# EEZ_Mosfet_pre-regulator_r3B3b_SS.net
KiCad netlist of a schematic drawn in EAGLE
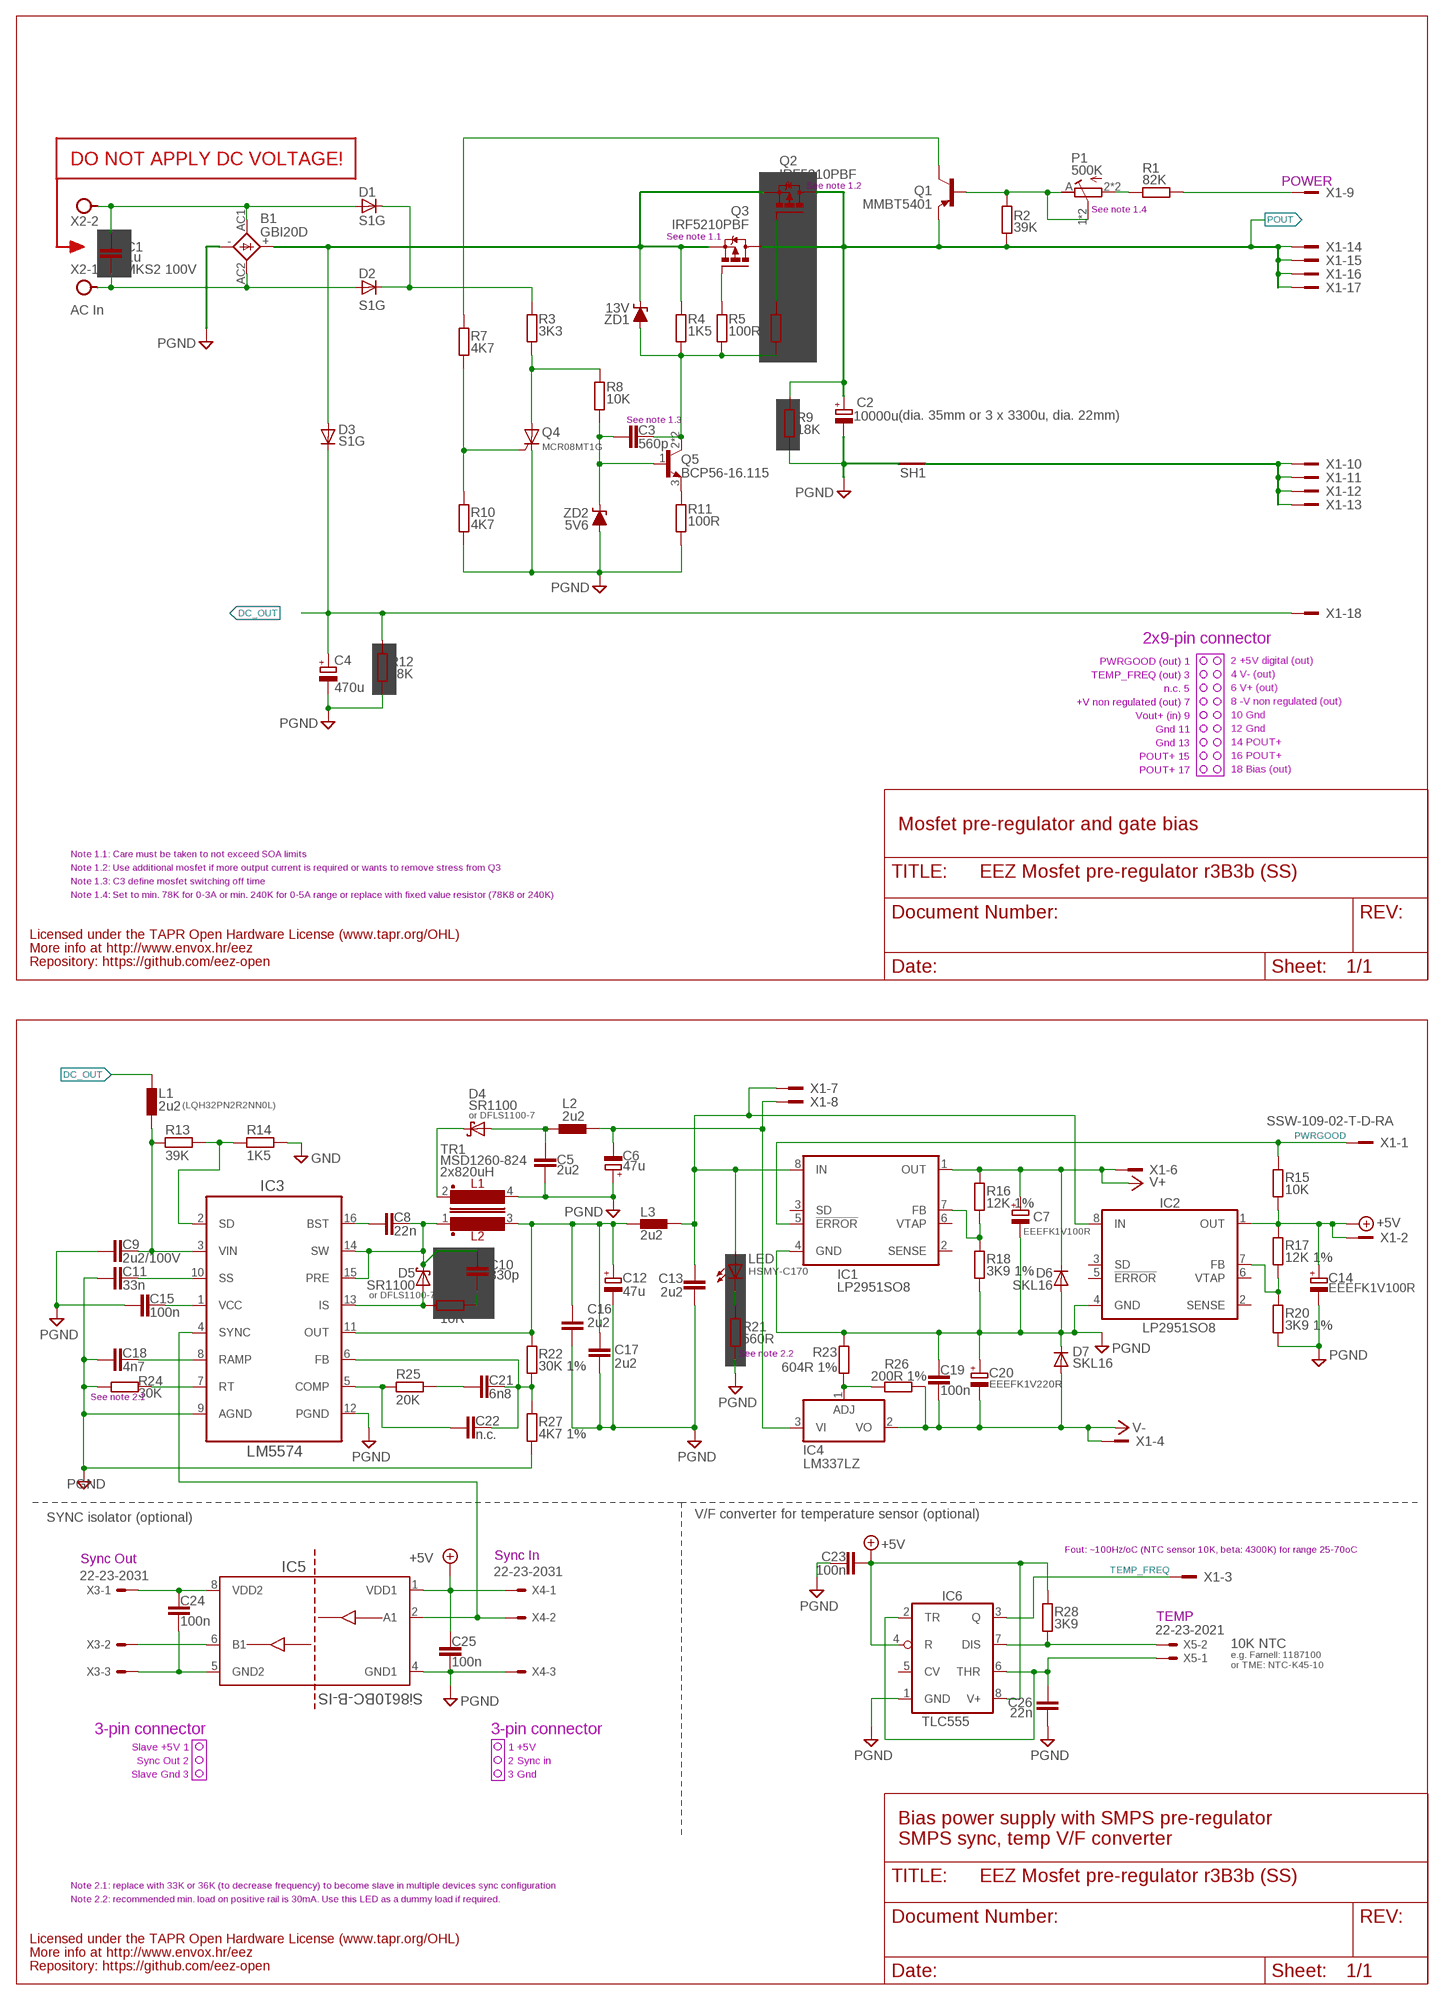
[diagram p0: schematic, sheet 1]

(export (version "E")
  (design (tool "Eeschema 10.0.6"))
  (components
    (comp (ref "B1")
      (value "GBI20D")
      (footprint "eagle-import:GBI20")
      (libsource (lib "eagle-import") (part "BRIDGEDIOTEC"))
    )
    (comp (ref "C1")
      (value "1u")
      (footprint "eagle-import:C050-075X075")
      (libsource (lib "eagle-import") (part "C-EU050-075X075"))
    )
    (comp (ref "C2")
      (value "10000u")
      (footprint "eagle-import:ED35D+3XED22.5_COMBO")
      (libsource (lib "eagle-import") (part "ECAP35+3X22.5"))
    )
    (comp (ref "C3")
      (value "560p")
      (footprint "eagle-import:C0805")
      (libsource (lib "eagle-import") (part "C-EUC0805"))
    )
    (comp (ref "C4")
      (value "470u")
      (footprint "eagle-import:ECAP5_13")
      (libsource (lib "eagle-import") (part "ECAP5G_13MM"))
    )
    (comp (ref "C5")
      (value "2u2")
      (footprint "eagle-import:C1210")
      (libsource (lib "eagle-import") (part "C-EUC1210"))
    )
    (comp (ref "C6")
      (value "47u")
      (footprint "eagle-import:CAPAE660X610N_COMBO")
      (libsource (lib "eagle-import") (part "ECAPEEEFK+8.5MM"))
    )
    (comp (ref "C7")
      (value "EEEFK1V100R")
      (footprint "eagle-import:CAPAE430X610N_COMBO")
      (libsource (lib "eagle-import") (part "ECAPEEEFK+5MM"))
    )
    (comp (ref "C8")
      (value "22n")
      (footprint "eagle-import:C0805")
      (libsource (lib "eagle-import") (part "C-EUC0805"))
    )
    (comp (ref "C9")
      (value "2u2/100V")
      (footprint "eagle-import:C1210")
      (libsource (lib "eagle-import") (part "C-EUC1210"))
    )
    (comp (ref "C10")
      (value "330p")
      (footprint "eagle-import:C0805")
      (libsource (lib "eagle-import") (part "C-EUC0805"))
    )
    (comp (ref "C11")
      (value "33n")
      (footprint "eagle-import:C0805")
      (libsource (lib "eagle-import") (part "C-EUC0805"))
    )
    (comp (ref "C12")
      (value "47u")
      (footprint "eagle-import:CAPAE660X610N_COMBO")
      (libsource (lib "eagle-import") (part "ECAPEEEFK+8.5MM"))
    )
    (comp (ref "C13")
      (value "2u2")
      (footprint "eagle-import:C1210")
      (libsource (lib "eagle-import") (part "C-EUC1210"))
    )
    (comp (ref "C14")
      (value "EEEFK1V100R")
      (footprint "eagle-import:CAPAE430X610N_COMBO")
      (libsource (lib "eagle-import") (part "ECAPEEEFK+5MM"))
    )
    (comp (ref "C15")
      (value "100n")
      (footprint "eagle-import:C0805")
      (libsource (lib "eagle-import") (part "C-EUC0805"))
    )
    (comp (ref "C16")
      (value "2u2")
      (footprint "eagle-import:C1210")
      (libsource (lib "eagle-import") (part "C-EUC1210"))
    )
    (comp (ref "C17")
      (value "2u2")
      (footprint "eagle-import:C1210")
      (libsource (lib "eagle-import") (part "C-EUC1210"))
    )
    (comp (ref "C18")
      (value "4n7")
      (footprint "eagle-import:C0805")
      (libsource (lib "eagle-import") (part "C-EUC0805"))
    )
    (comp (ref "C19")
      (value "100n")
      (footprint "eagle-import:C0805")
      (libsource (lib "eagle-import") (part "C-EUC0805"))
    )
    (comp (ref "C20")
      (value "EEEFK1V220R")
      (footprint "eagle-import:CAPAE430X610N_COMBO")
      (libsource (lib "eagle-import") (part "ECAPEEEFK+5MM"))
    )
    (comp (ref "C21")
      (value "6n8")
      (footprint "eagle-import:C0805")
      (libsource (lib "eagle-import") (part "C-EUC0805"))
    )
    (comp (ref "C22")
      (value "n.c.")
      (footprint "eagle-import:C0805")
      (libsource (lib "eagle-import") (part "C-EUC0805"))
    )
    (comp (ref "C23")
      (value "100n")
      (footprint "eagle-import:C0603")
      (libsource (lib "eagle-import") (part "C-EUC0603"))
    )
    (comp (ref "C24")
      (value "100n")
      (footprint "eagle-import:C0603")
      (libsource (lib "eagle-import") (part "C-EUC0603"))
    )
    (comp (ref "C25")
      (value "100n")
      (footprint "eagle-import:C0603")
      (libsource (lib "eagle-import") (part "C-EUC0603"))
    )
    (comp (ref "C26")
      (value "22n")
      (footprint "eagle-import:C0805")
      (libsource (lib "eagle-import") (part "C-EUC0805"))
    )
    (comp (ref "D1")
      (value "S1G")
      (footprint "eagle-import:DO214AC")
      (libsource (lib "eagle-import") (part "DIODE-DO214AC"))
    )
    (comp (ref "D2")
      (value "S1G")
      (footprint "eagle-import:DO214AC")
      (libsource (lib "eagle-import") (part "DIODE-DO214AC"))
    )
    (comp (ref "D3")
      (value "S1G")
      (footprint "eagle-import:DO214AC")
      (libsource (lib "eagle-import") (part "DIODE-DO214AC"))
    )
    (comp (ref "D4")
      (value "SR1100")
      (footprint "eagle-import:DO34+SOD123")
      (libsource (lib "eagle-import") (part "SCHOTTKYDO34+SOD123"))
    )
    (comp (ref "D5")
      (value "SR1100")
      (footprint "eagle-import:DO34+SOD123")
      (libsource (lib "eagle-import") (part "SCHOTTKYDO34+SOD123"))
    )
    (comp (ref "D6")
      (value "SKL16")
      (footprint "eagle-import:DO214AC")
      (libsource (lib "eagle-import") (part "DIODE-DO214AC"))
    )
    (comp (ref "D7")
      (value "SKL16")
      (footprint "eagle-import:DO214AC")
      (libsource (lib "eagle-import") (part "DIODE-DO214AC"))
    )
    (comp (ref "IC1")
      (value "LP2951SO8")
      (footprint "eagle-import:SOIC127P600X175-8N")
      (libsource (lib "eagle-import") (part "LP2951SO8"))
    )
    (comp (ref "IC2")
      (value "LP2951SO8")
      (footprint "eagle-import:SOIC127P600X175-8N")
      (libsource (lib "eagle-import") (part "LP2951SO8"))
    )
    (comp (ref "IC3")
      (value "LM5574")
      (footprint "eagle-import:SOP65P640X110-16N")
      (fields (field (name "MPN") "LM5574MT"))
      (libsource (lib "eagle-import") (part "LM5574"))
    )
    (comp (ref "IC4")
      (value "LM337LZ")
      (footprint "eagle-import:TO92")
      (libsource (lib "eagle-import") (part "337LZLM"))
    )
    (comp (ref "IC5")
      (value "Si8610BC-B-IS")
      (footprint "eagle-import:SOIC127P600X173-8N")
      (libsource (lib "eagle-import") (part "SI8610"))
    )
    (comp (ref "IC6")
      (value "TLC555")
      (footprint "eagle-import:SOIC127P600X175-8N")
      (libsource (lib "eagle-import") (part "LM555SOIC8"))
    )
    (comp (ref "L1")
      (value "2u2")
      (footprint "eagle-import:L1210_COMBO")
      (libsource (lib "eagle-import") (part "L1210COMBO"))
    )
    (comp (ref "L2")
      (value "2u2")
      (footprint "eagle-import:L1210_COMBO")
      (libsource (lib "eagle-import") (part "L1210COMBO"))
    )
    (comp (ref "L3")
      (value "2u2")
      (footprint "eagle-import:L1210_COMBO")
      (libsource (lib "eagle-import") (part "L1210COMBO"))
    )
    (comp (ref "LED")
      (value "HSMY-C170")
      (footprint "eagle-import:CHIPLED_0805")
      (libsource (lib "eagle-import") (part "LEDCHIPLED_0805"))
    )
    (comp (ref "P1")
      (value "500K")
      (footprint "eagle-import:R_TRIM+R0805")
      (libsource (lib "eagle-import") (part "R_TRIM_MIX0805"))
    )
    (comp (ref "Q1")
      (value "MMBT5401")
      (footprint "eagle-import:SOT23-BEC")
      (libsource (lib "eagle-import") (part "-PNP-SOT23-BECBC856B"))
    )
    (comp (ref "Q2")
      (value "IRF5210PBF")
      (footprint "eagle-import:TO220B-VMOS")
      (libsource (lib "eagle-import") (part "IRF9640"))
    )
    (comp (ref "Q3")
      (value "IRF5210PBF")
      (footprint "eagle-import:TO220B-VMOS")
      (libsource (lib "eagle-import") (part "IRF9640"))
    )
    (comp (ref "Q4")
      (value "MCR08MT1G")
      (footprint "eagle-import:SOT230P700X180-4N")
      (libsource (lib "eagle-import") (part "MCR08MT1G"))
    )
    (comp (ref "Q5")
      (value "BCP56-16.115")
      (footprint "eagle-import:SOT230P700X180-4N")
      (libsource (lib "eagle-import") (part "BCP56"))
    )
    (comp (ref "R1")
      (value "82K")
      (footprint "eagle-import:R0805")
      (libsource (lib "eagle-import") (part "R-EU_R0805"))
    )
    (comp (ref "R2")
      (value "39K")
      (footprint "eagle-import:R0805")
      (libsource (lib "eagle-import") (part "R-EU_R0805"))
    )
    (comp (ref "R3")
      (value "3K3")
      (footprint "eagle-import:R0805")
      (libsource (lib "eagle-import") (part "R-EU_R0805"))
    )
    (comp (ref "R4")
      (value "1K5")
      (footprint "eagle-import:R0805")
      (libsource (lib "eagle-import") (part "R-EU_R0805"))
    )
    (comp (ref "R5")
      (value "100R")
      (footprint "eagle-import:R0805")
      (libsource (lib "eagle-import") (part "R-EU_R0805"))
    )
    (comp (ref "R6")
      (value "100R")
      (footprint "eagle-import:R0805")
      (libsource (lib "eagle-import") (part "R-EU_R0805"))
    )
    (comp (ref "R7")
      (value "4K7")
      (footprint "eagle-import:R0805")
      (libsource (lib "eagle-import") (part "R-EU_R0805"))
    )
    (comp (ref "R8")
      (value "10K")
      (footprint "eagle-import:R0805")
      (libsource (lib "eagle-import") (part "R-EU_R0805"))
    )
    (comp (ref "R9")
      (value "18K")
      (footprint "eagle-import:R0805")
      (libsource (lib "eagle-import") (part "R-EU_R0805"))
    )
    (comp (ref "R10")
      (value "4K7")
      (footprint "eagle-import:R0805")
      (libsource (lib "eagle-import") (part "R-EU_R0805"))
    )
    (comp (ref "R11")
      (value "100R")
      (footprint "eagle-import:R0805")
      (libsource (lib "eagle-import") (part "R-EU_R0805"))
    )
    (comp (ref "R12")
      (value "18K")
      (footprint "eagle-import:R0805")
      (libsource (lib "eagle-import") (part "R-EU_R0805"))
    )
    (comp (ref "R13")
      (value "39K")
      (footprint "eagle-import:R0805")
      (libsource (lib "eagle-import") (part "R-EU_R0805"))
    )
    (comp (ref "R14")
      (value "1K5")
      (footprint "eagle-import:R0805")
      (libsource (lib "eagle-import") (part "R-EU_R0805"))
    )
    (comp (ref "R15")
      (value "10K")
      (footprint "eagle-import:R0805")
      (libsource (lib "eagle-import") (part "R-EU_R0805"))
    )
    (comp (ref "R16")
      (value "12K 1%")
      (footprint "eagle-import:R0805")
      (libsource (lib "eagle-import") (part "R-EU_R0805"))
    )
    (comp (ref "R17")
      (value "12K 1%")
      (footprint "eagle-import:R0805")
      (libsource (lib "eagle-import") (part "R-EU_R0805"))
    )
    (comp (ref "R18")
      (value "3K9 1%")
      (footprint "eagle-import:R0805")
      (libsource (lib "eagle-import") (part "R-EU_R0805"))
    )
    (comp (ref "R19")
      (value "10R")
      (footprint "eagle-import:R1210")
      (libsource (lib "eagle-import") (part "R-EU_R1210"))
    )
    (comp (ref "R20")
      (value "3K9 1%")
      (footprint "eagle-import:R0805")
      (libsource (lib "eagle-import") (part "R-EU_R0805"))
    )
    (comp (ref "R21")
      (value "560R")
      (footprint "eagle-import:R0805")
      (libsource (lib "eagle-import") (part "R-EU_R0805"))
    )
    (comp (ref "R22")
      (value "30K 1%")
      (footprint "eagle-import:R0805")
      (libsource (lib "eagle-import") (part "R-EU_R0805"))
    )
    (comp (ref "R23")
      (value "604R 1%")
      (footprint "eagle-import:R0805")
      (libsource (lib "eagle-import") (part "R-EU_R0805"))
    )
    (comp (ref "R24")
      (value "30K")
      (footprint "eagle-import:R0805")
      (libsource (lib "eagle-import") (part "R-EU_R0805"))
    )
    (comp (ref "R25")
      (value "20K")
      (footprint "eagle-import:R0805")
      (libsource (lib "eagle-import") (part "R-EU_R0805"))
    )
    (comp (ref "R26")
      (value "200R 1%")
      (footprint "eagle-import:R0805")
      (libsource (lib "eagle-import") (part "R-EU_R0805"))
    )
    (comp (ref "R27")
      (value "4K7 1%")
      (footprint "eagle-import:R0805")
      (libsource (lib "eagle-import") (part "R-EU_R0805"))
    )
    (comp (ref "R28")
      (value "3K9")
      (footprint "eagle-import:R0805")
      (libsource (lib "eagle-import") (part "R-EU_R0805"))
    )
    (comp (ref "SH1")
      (value "SHORTH")
      (footprint "eagle-import:SHORT_2")
      (libsource (lib "eagle-import") (part "SHORTH"))
    )
    (comp (ref "TR1")
      (value "MSD1260-824")
      (footprint "eagle-import:MSD1260")
      (libsource (lib "eagle-import") (part "COILCRAFT_MSD1260INV"))
    )
    (comp (ref "X1")
      (value "SSW-109-02-T-D-RA")
      (footprint "eagle-import:SSW-109-02-T-D-RA")
      (fields (field (name "FARNELL") "1804359"))
      (libsource (lib "eagle-import") (part "SSW-109-02-T-D-RA"))
    )
    (comp (ref "X2")
      (value "AC In")
      (footprint "eagle-import:TBLOCK5.0_2")
      (libsource (lib "eagle-import") (part "TBLOCK5.0_2A"))
    )
    (comp (ref "X3")
      (value "22-23-2031")
      (footprint "eagle-import:22-23-2031")
      (fields
        (field (name "MF") "MOLEX")
        (field (name "MF_1") "MOLEX")
        (field (name "MPN") "22-23-2031")
        (field (name "OC_FARNELL") "1462950")
        (field (name "OC_NEWARK") "30C0862")
      )
      (libsource (lib "eagle-import") (part "22-23-2031"))
    )
    (comp (ref "X4")
      (value "22-23-2031")
      (footprint "eagle-import:22-23-2031")
      (fields
        (field (name "MF") "MOLEX")
        (field (name "MF_1") "MOLEX")
        (field (name "MPN") "22-23-2031")
        (field (name "OC_FARNELL") "1462950")
        (field (name "OC_NEWARK") "30C0862")
      )
      (libsource (lib "eagle-import") (part "22-23-2031"))
    )
    (comp (ref "X5")
      (value "22-23-2021")
      (footprint "eagle-import:22-23-2021")
      (fields (field (name "MF") "MOLEX"))
      (libsource (lib "eagle-import") (part "22-23-2021"))
    )
    (comp (ref "ZD1")
      (value "13V")
      (footprint "eagle-import:MINIMELF")
      (libsource (lib "eagle-import") (part "ZENER-DIODEMINIMELF"))
    )
    (comp (ref "ZD2")
      (value "5V6")
      (footprint "eagle-import:MINIMELF")
      (libsource (lib "eagle-import") (part "ZENER-DIODEMINIMELF"))
    )
  )
  (nets
    (net (code "1") (name "+5V") (class "Default")
      (node (ref "C14") (pin "1") (pinfunction "+_1") (pintype "passive"))
      (node (ref "C14") (pin "1.1") (pinfunction "+_1.1") (pintype "passive"))
      (node (ref "C23") (pin "1") (pinfunction "1_1") (pintype "passive"))
      (node (ref "C25") (pin "1") (pinfunction "1_1") (pintype "passive"))
      (node (ref "IC2") (pin "1") (pinfunction "OUT_1") (pintype "output"))
      (node (ref "IC5") (pin "1") (pinfunction "VDD1_1") (pintype "power_in"))
      (node (ref "IC6") (pin "4") (pinfunction "R_4") (pintype "input"))
      (node (ref "IC6") (pin "8") (pinfunction "V+_8") (pintype "power_in"))
      (node (ref "R15") (pin "2") (pinfunction "2_2") (pintype "passive"))
      (node (ref "R17") (pin "1") (pinfunction "1_1") (pintype "passive"))
      (node (ref "R28") (pin "2") (pinfunction "2_2") (pintype "passive"))
      (node (ref "X1") (pin "2") (pinfunction "KL_2") (pintype "passive"))
      (node (ref "X4") (pin "1") (pinfunction "S_1") (pintype "passive"))
    )
    (net (code "2") (name "/PWRGOOD") (class "Default")
      (node (ref "IC1") (pin "5") (pinfunction "~{ERROR}_5") (pintype "input"))
      (node (ref "R15") (pin "1") (pinfunction "1_1") (pintype "passive"))
      (node (ref "X1") (pin "1") (pinfunction "KL_1") (pintype "passive"))
    )
    (net (code "3") (name "/TEMP_FREQ") (class "Default")
      (node (ref "IC6") (pin "3") (pinfunction "Q_3") (pintype "output"))
      (node (ref "X1") (pin "3") (pinfunction "KL_3") (pintype "passive"))
    )
    (net (code "4") (name "DC_OUT") (class "Default")
      (node (ref "C4") (pin "+") (pinfunction "+_+") (pintype "passive"))
      (node (ref "D3") (pin "C") (pinfunction "C_C") (pintype "passive"))
      (node (ref "L1") (pin "1") (pinfunction "1_1") (pintype "passive"))
      (node (ref "L1") (pin "1.1") (pinfunction "1_1.1") (pintype "passive"))
      (node (ref "R12") (pin "1") (pinfunction "1_1") (pintype "passive"))
      (node (ref "X1") (pin "18") (pinfunction "KL_18") (pintype "passive"))
    )
    (net (code "5") (name "GND") (class "Default")
      (node (ref "B1") (pin "-") (pinfunction "-_-") (pintype "passive"))
      (node (ref "C11") (pin "2") (pinfunction "2_2") (pintype "passive"))
      (node (ref "C12") (pin "2") (pinfunction "-_2") (pintype "passive"))
      (node (ref "C12") (pin "2.1") (pinfunction "-_2.1") (pintype "passive"))
      (node (ref "C13") (pin "2") (pinfunction "2_2") (pintype "passive"))
      (node (ref "C14") (pin "2") (pinfunction "-_2") (pintype "passive"))
      (node (ref "C14") (pin "2.1") (pinfunction "-_2.1") (pintype "passive"))
      (node (ref "C15") (pin "1") (pinfunction "1_1") (pintype "passive"))
      (node (ref "C16") (pin "2") (pinfunction "2_2") (pintype "passive"))
      (node (ref "C17") (pin "2") (pinfunction "2_2") (pintype "passive"))
      (node (ref "C18") (pin "1") (pinfunction "1_1") (pintype "passive"))
      (node (ref "C19") (pin "1") (pinfunction "1_1") (pintype "passive"))
      (node (ref "C2") (pin "-") (pinfunction "-_-") (pintype "passive"))
      (node (ref "C2") (pin "-1") (pinfunction "-_-1") (pintype "passive"))
      (node (ref "C2") (pin "-2") (pinfunction "-_-2") (pintype "passive"))
      (node (ref "C2") (pin "-3") (pinfunction "-_-3") (pintype "passive"))
      (node (ref "C20") (pin "1") (pinfunction "+_1") (pintype "passive"))
      (node (ref "C20") (pin "1.1") (pinfunction "+_1.1") (pintype "passive"))
      (node (ref "C23") (pin "2") (pinfunction "2_2") (pintype "passive"))
      (node (ref "C25") (pin "2") (pinfunction "2_2") (pintype "passive"))
      (node (ref "C26") (pin "1") (pinfunction "1_1") (pintype "passive"))
      (node (ref "C4") (pin "-") (pinfunction "-_-") (pintype "passive"))
      (node (ref "C5") (pin "2") (pinfunction "2_2") (pintype "passive"))
      (node (ref "C6") (pin "1") (pinfunction "+_1") (pintype "passive"))
      (node (ref "C6") (pin "1.1") (pinfunction "+_1.1") (pintype "passive"))
      (node (ref "C7") (pin "2") (pinfunction "-_2") (pintype "passive"))
      (node (ref "C7") (pin "2.1") (pinfunction "-_2.1") (pintype "passive"))
      (node (ref "C9") (pin "2") (pinfunction "2_2") (pintype "passive"))
      (node (ref "D6") (pin "A") (pinfunction "A_A") (pintype "passive"))
      (node (ref "D7") (pin "C") (pinfunction "C_C") (pintype "passive"))
      (node (ref "IC1") (pin "4") (pinfunction "GND_4") (pintype "passive"))
      (node (ref "IC2") (pin "4") (pinfunction "GND_4") (pintype "passive"))
      (node (ref "IC3") (pin "12") (pinfunction "PGND_12") (pintype "passive"))
      (node (ref "IC3") (pin "9") (pinfunction "AGND_9") (pintype "passive"))
      (node (ref "IC5") (pin "4") (pinfunction "GND1_4") (pintype "power_in"))
      (node (ref "IC6") (pin "1") (pinfunction "GND_1") (pintype "power_in"))
      (node (ref "Q4") (pin "1") (pinfunction "C_1") (pintype "passive"))
      (node (ref "R10") (pin "2") (pinfunction "2_2") (pintype "passive"))
      (node (ref "R11") (pin "2") (pinfunction "2_2") (pintype "passive"))
      (node (ref "R12") (pin "2") (pinfunction "2_2") (pintype "passive"))
      (node (ref "R14") (pin "1") (pinfunction "1_1") (pintype "passive"))
      (node (ref "R18") (pin "2") (pinfunction "2_2") (pintype "passive"))
      (node (ref "R20") (pin "2") (pinfunction "2_2") (pintype "passive"))
      (node (ref "R21") (pin "2") (pinfunction "2_2") (pintype "passive"))
      (node (ref "R23") (pin "2") (pinfunction "2_2") (pintype "passive"))
      (node (ref "R24") (pin "2") (pinfunction "2_2") (pintype "passive"))
      (node (ref "R27") (pin "2") (pinfunction "2_2") (pintype "passive"))
      (node (ref "R9") (pin "2") (pinfunction "2_2") (pintype "passive"))
      (node (ref "SH1") (pin "2") (pinfunction "GND_B_2") (pintype "bidirectional"))
      (node (ref "TR1") (pin "4") (pinfunction "4_4") (pintype "passive"))
      (node (ref "X4") (pin "3") (pinfunction "S_3") (pintype "passive"))
      (node (ref "ZD2") (pin "A") (pinfunction "A_A") (pintype "passive"))
    )
    (net (code "6") (name "Net-(B1-Pad+)") (class "Default")
      (node (ref "B1") (pin "+") (pinfunction "+_+") (pintype "passive"))
      (node (ref "D3") (pin "A") (pinfunction "A_A") (pintype "passive"))
      (node (ref "Q2") (pin "S") (pinfunction "S_S") (pintype "passive"))
      (node (ref "Q3") (pin "S") (pinfunction "S_S") (pintype "passive"))
      (node (ref "R4") (pin "1") (pinfunction "1_1") (pintype "passive"))
      (node (ref "ZD1") (pin "C") (pinfunction "C_C") (pintype "passive"))
    )
    (net (code "7") (name "Net-(B1-PadAC2)") (class "Default")
      (node (ref "B1") (pin "AC2") (pinfunction "AC2_AC2") (pintype "passive"))
      (node (ref "C1") (pin "2") (pinfunction "2_2") (pintype "passive"))
      (node (ref "D2") (pin "A") (pinfunction "A_A") (pintype "passive"))
      (node (ref "X2") (pin "1") (pinfunction "1_1") (pintype "bidirectional"))
    )
    (net (code "8") (name "Net-(C3-Pad1)") (class "Default")
      (node (ref "C3") (pin "1") (pinfunction "1_1") (pintype "passive"))
      (node (ref "Q5") (pin "2") (pinfunction "C_2") (pintype "passive"))
      (node (ref "Q5") (pin "4") (pinfunction "C_4") (pintype "passive"))
      (node (ref "R4") (pin "2") (pinfunction "2_2") (pintype "passive"))
      (node (ref "R5") (pin "2") (pinfunction "2_2") (pintype "passive"))
      (node (ref "R6") (pin "2") (pinfunction "2_2") (pintype "passive"))
      (node (ref "ZD1") (pin "A") (pinfunction "A_A") (pintype "passive"))
    )
    (net (code "9") (name "Net-(C5-Pad1)") (class "Default")
      (node (ref "C5") (pin "1") (pinfunction "1_1") (pintype "passive"))
      (node (ref "D4") (pin "A") (pinfunction "A_A") (pintype "passive"))
      (node (ref "D4") (pin "A.1") (pinfunction "A_A.1") (pintype "passive"))
      (node (ref "L2") (pin "1") (pinfunction "1_1") (pintype "passive"))
      (node (ref "L2") (pin "1.1") (pinfunction "1_1.1") (pintype "passive"))
    )
    (net (code "10") (name "Net-(C10-Pad2)") (class "Default")
      (node (ref "C10") (pin "2") (pinfunction "2_2") (pintype "passive"))
      (node (ref "R19") (pin "2") (pinfunction "2_2") (pintype "passive"))
    )
    (net (code "11") (name "Net-(C21-Pad2)") (class "Default")
      (node (ref "C21") (pin "2") (pinfunction "2_2") (pintype "passive"))
      (node (ref "R25") (pin "2") (pinfunction "2_2") (pintype "passive"))
    )
    (net (code "12") (name "Net-(D1-PadC)") (class "Default")
      (node (ref "D1") (pin "C") (pinfunction "C_C") (pintype "passive"))
      (node (ref "D2") (pin "C") (pinfunction "C_C") (pintype "passive"))
      (node (ref "R3") (pin "1") (pinfunction "1_1") (pintype "passive"))
    )
    (net (code "13") (name "Net-(D4-C-PadC.1)") (class "Default")
      (node (ref "D4") (pin "C") (pinfunction "C_C") (pintype "passive"))
      (node (ref "D4") (pin "C.1") (pinfunction "C_C.1") (pintype "passive"))
      (node (ref "TR1") (pin "2") (pinfunction "2_2") (pintype "passive"))
    )
    (net (code "14") (name "Net-(IC1-FB)") (class "Default")
      (node (ref "IC1") (pin "7") (pinfunction "FB_7") (pintype "input"))
      (node (ref "R16") (pin "2") (pinfunction "2_2") (pintype "passive"))
      (node (ref "R18") (pin "1") (pinfunction "1_1") (pintype "passive"))
    )
    (net (code "15") (name "Net-(IC1-IN)") (class "Default")
      (node (ref "C13") (pin "1") (pinfunction "1_1") (pintype "passive"))
      (node (ref "IC1") (pin "8") (pinfunction "IN_8") (pintype "power_in"))
      (node (ref "IC2") (pin "8") (pinfunction "IN_8") (pintype "power_in"))
      (node (ref "L3") (pin "2") (pinfunction "2_2") (pintype "passive"))
      (node (ref "L3") (pin "2.1") (pinfunction "2_2.1") (pintype "passive"))
      (node (ref "LED") (pin "A") (pinfunction "A_A") (pintype "passive"))
      (node (ref "X1") (pin "7") (pinfunction "KL_7") (pintype "passive"))
    )
    (net (code "16") (name "Net-(IC2-FB)") (class "Default")
      (node (ref "IC2") (pin "7") (pinfunction "FB_7") (pintype "input"))
      (node (ref "R17") (pin "2") (pinfunction "2_2") (pintype "passive"))
      (node (ref "R20") (pin "1") (pinfunction "1_1") (pintype "passive"))
    )
    (net (code "17") (name "Net-(IC3-BST)") (class "Default")
      (node (ref "C8") (pin "2") (pinfunction "2_2") (pintype "passive"))
      (node (ref "IC3") (pin "16") (pinfunction "BST_16") (pintype "input"))
    )
    (net (code "18") (name "Net-(IC3-COMP)") (class "Default")
      (node (ref "C22") (pin "2") (pinfunction "2_2") (pintype "passive"))
      (node (ref "IC3") (pin "5") (pinfunction "COMP_5") (pintype "input"))
      (node (ref "R25") (pin "1") (pinfunction "1_1") (pintype "passive"))
    )
    (net (code "19") (name "Net-(IC3-FB)") (class "Default")
      (node (ref "C21") (pin "1") (pinfunction "1_1") (pintype "passive"))
      (node (ref "C22") (pin "1") (pinfunction "1_1") (pintype "passive"))
      (node (ref "IC3") (pin "6") (pinfunction "FB_6") (pintype "input"))
      (node (ref "R22") (pin "2") (pinfunction "2_2") (pintype "passive"))
      (node (ref "R27") (pin "1") (pinfunction "1_1") (pintype "passive"))
    )
    (net (code "20") (name "Net-(IC3-IS)") (class "Default")
      (node (ref "D5") (pin "A") (pinfunction "A_A") (pintype "passive"))
      (node (ref "D5") (pin "A.1") (pinfunction "A_A.1") (pintype "passive"))
      (node (ref "IC3") (pin "13") (pinfunction "IS_13") (pintype "input"))
      (node (ref "R19") (pin "1") (pinfunction "1_1") (pintype "passive"))
    )
    (net (code "21") (name "Net-(IC3-OUT)") (class "Default")
      (node (ref "C12") (pin "1") (pinfunction "+_1") (pintype "passive"))
      (node (ref "C12") (pin "1.1") (pinfunction "+_1.1") (pintype "passive"))
      (node (ref "C16") (pin "1") (pinfunction "1_1") (pintype "passive"))
      (node (ref "C17") (pin "1") (pinfunction "1_1") (pintype "passive"))
      (node (ref "IC3") (pin "11") (pinfunction "OUT_11") (pintype "output"))
      (node (ref "L3") (pin "1") (pinfunction "1_1") (pintype "passive"))
      (node (ref "L3") (pin "1.1") (pinfunction "1_1.1") (pintype "passive"))
      (node (ref "R22") (pin "1") (pinfunction "1_1") (pintype "passive"))
      (node (ref "TR1") (pin "3") (pinfunction "3_3") (pintype "passive"))
    )
    (net (code "22") (name "Net-(IC3-PRE)") (class "Default")
      (node (ref "C10") (pin "1") (pinfunction "1_1") (pintype "passive"))
      (node (ref "C8") (pin "1") (pinfunction "1_1") (pintype "passive"))
      (node (ref "D5") (pin "C") (pinfunction "C_C") (pintype "passive"))
      (node (ref "D5") (pin "C.1") (pinfunction "C_C.1") (pintype "passive"))
      (node (ref "IC3") (pin "14") (pinfunction "SW_14") (pintype "output"))
      (node (ref "IC3") (pin "15") (pinfunction "PRE_15") (pintype "input"))
      (node (ref "TR1") (pin "1") (pinfunction "1_1") (pintype "passive"))
    )
    (net (code "23") (name "Net-(IC3-RAMP)") (class "Default")
      (node (ref "C18") (pin "2") (pinfunction "2_2") (pintype "passive"))
      (node (ref "IC3") (pin "8") (pinfunction "RAMP_8") (pintype "input"))
    )
    (net (code "24") (name "Net-(IC3-RT)") (class "Default")
      (node (ref "IC3") (pin "7") (pinfunction "RT_7") (pintype "input"))
      (node (ref "R24") (pin "1") (pinfunction "1_1") (pintype "passive"))
    )
    (net (code "25") (name "Net-(IC3-SD)") (class "Default")
      (node (ref "IC3") (pin "2") (pinfunction "SD_2") (pintype "input"))
      (node (ref "R13") (pin "1") (pinfunction "1_1") (pintype "passive"))
      (node (ref "R14") (pin "2") (pinfunction "2_2") (pintype "passive"))
    )
    (net (code "26") (name "Net-(IC3-SS)") (class "Default")
      (node (ref "C11") (pin "1") (pinfunction "1_1") (pintype "passive"))
      (node (ref "IC3") (pin "10") (pinfunction "SS_10") (pintype "input"))
    )
    (net (code "27") (name "Net-(IC3-SYNC)") (class "Default")
      (node (ref "IC3") (pin "4") (pinfunction "SYNC_4") (pintype "input"))
      (node (ref "IC5") (pin "2") (pinfunction "A1_2") (pintype "input"))
      (node (ref "X4") (pin "2") (pinfunction "S_2") (pintype "passive"))
    )
    (net (code "28") (name "Net-(IC3-VCC)") (class "Default")
      (node (ref "C15") (pin "2") (pinfunction "2_2") (pintype "passive"))
      (node (ref "IC3") (pin "1") (pinfunction "VCC_1") (pintype "power_in"))
    )
    (net (code "29") (name "Net-(IC3-VIN)") (class "Default")
      (node (ref "C9") (pin "1") (pinfunction "1_1") (pintype "passive"))
      (node (ref "IC3") (pin "3") (pinfunction "VIN_3") (pintype "input"))
      (node (ref "L1") (pin "2") (pinfunction "2_2") (pintype "passive"))
      (node (ref "L1") (pin "2.1") (pinfunction "2_2.1") (pintype "passive"))
      (node (ref "R13") (pin "2") (pinfunction "2_2") (pintype "passive"))
    )
    (net (code "30") (name "Net-(IC4-ADJ)") (class "Default")
      (node (ref "IC4") (pin "1") (pinfunction "ADJ_1") (pintype "input"))
      (node (ref "R23") (pin "1") (pinfunction "1_1") (pintype "passive"))
      (node (ref "R26") (pin "2") (pinfunction "2_2") (pintype "passive"))
    )
    (net (code "31") (name "Net-(IC4-VI)") (class "Default")
      (node (ref "C6") (pin "2") (pinfunction "-_2") (pintype "passive"))
      (node (ref "C6") (pin "2.1") (pinfunction "-_2.1") (pintype "passive"))
      (node (ref "IC4") (pin "3") (pinfunction "VI_3") (pintype "input"))
      (node (ref "L2") (pin "2") (pinfunction "2_2") (pintype "passive"))
      (node (ref "L2") (pin "2.1") (pinfunction "2_2.1") (pintype "passive"))
      (node (ref "X1") (pin "8") (pinfunction "KL_8") (pintype "passive"))
    )
    (net (code "32") (name "Net-(IC5-B1)") (class "Default")
      (node (ref "IC5") (pin "6") (pinfunction "B1_6") (pintype "output"))
      (node (ref "X3") (pin "2") (pinfunction "S_2") (pintype "passive"))
    )
    (net (code "33") (name "Net-(IC5-GND2)") (class "Default")
      (node (ref "C24") (pin "2") (pinfunction "2_2") (pintype "passive"))
      (node (ref "IC5") (pin "5") (pinfunction "GND2_5") (pintype "power_in"))
      (node (ref "X3") (pin "3") (pinfunction "S_3") (pintype "passive"))
    )
    (net (code "34") (name "Net-(IC5-VDD2)") (class "Default")
      (node (ref "C24") (pin "1") (pinfunction "1_1") (pintype "passive"))
      (node (ref "IC5") (pin "8") (pinfunction "VDD2_8") (pintype "power_in"))
      (node (ref "X3") (pin "1") (pinfunction "S_1") (pintype "passive"))
    )
    (net (code "35") (name "Net-(IC6-DIS)") (class "Default")
      (node (ref "IC6") (pin "7") (pinfunction "DIS_7") (pintype "input"))
      (node (ref "R28") (pin "1") (pinfunction "1_1") (pintype "passive"))
      (node (ref "X5") (pin "2") (pinfunction "S_2") (pintype "passive"))
    )
    (net (code "36") (name "Net-(IC6-THR)") (class "Default")
      (node (ref "C26") (pin "2") (pinfunction "2_2") (pintype "passive"))
      (node (ref "IC6") (pin "2") (pinfunction "TR_2") (pintype "input"))
      (node (ref "IC6") (pin "6") (pinfunction "THR_6") (pintype "input"))
      (node (ref "X5") (pin "1") (pinfunction "S_1") (pintype "passive"))
    )
    (net (code "37") (name "Net-(LED-PadC)") (class "Default")
      (node (ref "LED") (pin "C") (pinfunction "C_C") (pintype "passive"))
      (node (ref "R21") (pin "1") (pinfunction "1_1") (pintype "passive"))
    )
    (net (code "38") (name "Net-(P1-E-Pad2)") (class "Default")
      (node (ref "P1") (pin "2") (pinfunction "E_2") (pintype "passive"))
      (node (ref "P1") (pin "E") (pinfunction "E_E") (pintype "passive"))
      (node (ref "R1") (pin "1") (pinfunction "1_1") (pintype "passive"))
    )
    (net (code "39") (name "Net-(P1-PadA)") (class "Default")
      (node (ref "P1") (pin "1") (pinfunction "S_1") (pintype "passive"))
      (node (ref "P1") (pin "A") (pinfunction "A_A") (pintype "passive"))
      (node (ref "P1") (pin "S") (pinfunction "S_S") (pintype "passive"))
      (node (ref "Q1") (pin "B") (pinfunction "B_B") (pintype "passive"))
      (node (ref "R2") (pin "1") (pinfunction "1_1") (pintype "passive"))
    )
    (net (code "40") (name "Net-(Q1-PadC)") (class "Default")
      (node (ref "Q1") (pin "C") (pinfunction "C_C") (pintype "passive"))
      (node (ref "R7") (pin "1") (pinfunction "1_1") (pintype "passive"))
    )
    (net (code "41") (name "Net-(Q2-PadG)") (class "Default")
      (node (ref "Q2") (pin "G") (pinfunction "G_G") (pintype "passive"))
      (node (ref "R6") (pin "1") (pinfunction "1_1") (pintype "passive"))
    )
    (net (code "42") (name "Net-(Q3-PadG)") (class "Default")
      (node (ref "Q3") (pin "G") (pinfunction "G_G") (pintype "passive"))
      (node (ref "R5") (pin "1") (pinfunction "1_1") (pintype "passive"))
    )
    (net (code "43") (name "Net-(Q4-A-Pad2)") (class "Default")
      (node (ref "Q4") (pin "2") (pinfunction "A_2") (pintype "passive"))
      (node (ref "Q4") (pin "4") (pinfunction "A_4") (pintype "passive"))
      (node (ref "R3") (pin "2") (pinfunction "2_2") (pintype "passive"))
      (node (ref "R8") (pin "1") (pinfunction "1_1") (pintype "passive"))
    )
    (net (code "44") (name "Net-(Q4-G)") (class "Default")
      (node (ref "Q4") (pin "3") (pinfunction "G_3") (pintype "passive"))
      (node (ref "R10") (pin "1") (pinfunction "1_1") (pintype "passive"))
      (node (ref "R7") (pin "2") (pinfunction "2_2") (pintype "passive"))
    )
    (net (code "45") (name "Net-(Q5-B)") (class "Default")
      (node (ref "C3") (pin "2") (pinfunction "2_2") (pintype "passive"))
      (node (ref "Q5") (pin "1") (pinfunction "B_1") (pintype "passive"))
      (node (ref "R8") (pin "2") (pinfunction "2_2") (pintype "passive"))
      (node (ref "ZD2") (pin "C") (pinfunction "C_C") (pintype "passive"))
    )
    (net (code "46") (name "Net-(Q5-E)") (class "Default")
      (node (ref "Q5") (pin "3") (pinfunction "E_3") (pintype "passive"))
      (node (ref "R11") (pin "1") (pinfunction "1_1") (pintype "passive"))
    )
    (net (code "47") (name "Net-(SH1-GND_A)") (class "Default")
      (node (ref "SH1") (pin "1") (pinfunction "GND_A_1") (pintype "bidirectional"))
      (node (ref "X1") (pin "10") (pinfunction "KL_10") (pintype "passive"))
      (node (ref "X1") (pin "11") (pinfunction "KL_11") (pintype "passive"))
      (node (ref "X1") (pin "12") (pinfunction "KL_12") (pintype "passive"))
      (node (ref "X1") (pin "13") (pinfunction "KL_13") (pintype "passive"))
    )
    (net (code "48") (name "Net-(X1R-KL)") (class "Default")
      (node (ref "R1") (pin "2") (pinfunction "2_2") (pintype "passive"))
      (node (ref "X1") (pin "9") (pinfunction "KL_9") (pintype "passive"))
    )
    (net (code "49") (name "Net-(X2B-1)") (class "Default")
      (node (ref "B1") (pin "AC1") (pinfunction "AC1_AC1") (pintype "passive"))
      (node (ref "C1") (pin "1") (pinfunction "1_1") (pintype "passive"))
      (node (ref "D1") (pin "A") (pinfunction "A_A") (pintype "passive"))
      (node (ref "X2") (pin "2") (pinfunction "1_2") (pintype "bidirectional"))
    )
    (net (code "50") (name "POUT") (class "Default")
      (node (ref "C2") (pin "+") (pinfunction "+_+") (pintype "passive"))
      (node (ref "C2") (pin "+2") (pinfunction "+_+2") (pintype "passive"))
      (node (ref "C2") (pin "+3") (pinfunction "+_+3") (pintype "passive"))
      (node (ref "Q1") (pin "E") (pinfunction "E_E") (pintype "passive"))
      (node (ref "Q2") (pin "D") (pinfunction "D_D") (pintype "passive"))
      (node (ref "Q3") (pin "D") (pinfunction "D_D") (pintype "passive"))
      (node (ref "R2") (pin "2") (pinfunction "2_2") (pintype "passive"))
      (node (ref "R9") (pin "1") (pinfunction "1_1") (pintype "passive"))
      (node (ref "X1") (pin "14") (pinfunction "KL_14") (pintype "passive"))
      (node (ref "X1") (pin "15") (pinfunction "KL_15") (pintype "passive"))
      (node (ref "X1") (pin "16") (pinfunction "KL_16") (pintype "passive"))
      (node (ref "X1") (pin "17") (pinfunction "KL_17") (pintype "passive"))
    )
    (net (code "51") (name "V+") (class "Default")
      (node (ref "C7") (pin "1") (pinfunction "+_1") (pintype "passive"))
      (node (ref "C7") (pin "1.1") (pinfunction "+_1.1") (pintype "passive"))
      (node (ref "D6") (pin "C") (pinfunction "C_C") (pintype "passive"))
      (node (ref "IC1") (pin "1") (pinfunction "OUT_1") (pintype "output"))
      (node (ref "R16") (pin "1") (pinfunction "1_1") (pintype "passive"))
      (node (ref "X1") (pin "6") (pinfunction "KL_6") (pintype "passive"))
    )
    (net (code "52") (name "V-") (class "Default")
      (node (ref "C19") (pin "2") (pinfunction "2_2") (pintype "passive"))
      (node (ref "C20") (pin "2") (pinfunction "-_2") (pintype "passive"))
      (node (ref "C20") (pin "2.1") (pinfunction "-_2.1") (pintype "passive"))
      (node (ref "D7") (pin "A") (pinfunction "A_A") (pintype "passive"))
      (node (ref "IC4") (pin "2") (pinfunction "VO_2") (pintype "passive"))
      (node (ref "R26") (pin "1") (pinfunction "1_1") (pintype "passive"))
      (node (ref "X1") (pin "4") (pinfunction "KL_4") (pintype "passive"))
    )
    (net (code "53") (name "unconnected-(IC1-SD-Pad3)") (class "Default")
      (node (ref "IC1") (pin "3") (pinfunction "SD_3") (pintype "input"))
    )
    (net (code "54") (name "unconnected-(IC1-SENSE-Pad2)") (class "Default")
      (node (ref "IC1") (pin "2") (pinfunction "SENSE_2") (pintype "input"))
    )
    (net (code "55") (name "unconnected-(IC1-VTAP-Pad6)") (class "Default")
      (node (ref "IC1") (pin "6") (pinfunction "VTAP_6") (pintype "input"))
    )
    (net (code "56") (name "unconnected-(IC2-SD-Pad3)") (class "Default")
      (node (ref "IC2") (pin "3") (pinfunction "SD_3") (pintype "input"))
    )
    (net (code "57") (name "unconnected-(IC2-SENSE-Pad2)") (class "Default")
      (node (ref "IC2") (pin "2") (pinfunction "SENSE_2") (pintype "input"))
    )
    (net (code "58") (name "unconnected-(IC2-VTAP-Pad6)") (class "Default")
      (node (ref "IC2") (pin "6") (pinfunction "VTAP_6") (pintype "input"))
    )
    (net (code "59") (name "unconnected-(IC2-~{ERROR}-Pad5)") (class "Default")
      (node (ref "IC2") (pin "5") (pinfunction "~{ERROR}_5") (pintype "input"))
    )
    (net (code "60") (name "unconnected-(IC6-CV-Pad5)") (class "Default")
      (node (ref "IC6") (pin "5") (pinfunction "CV_5") (pintype "input"))
    )
  )
)
